# BB_AMP.net
KiCad netlist of a schematic drawn in Altium Designer
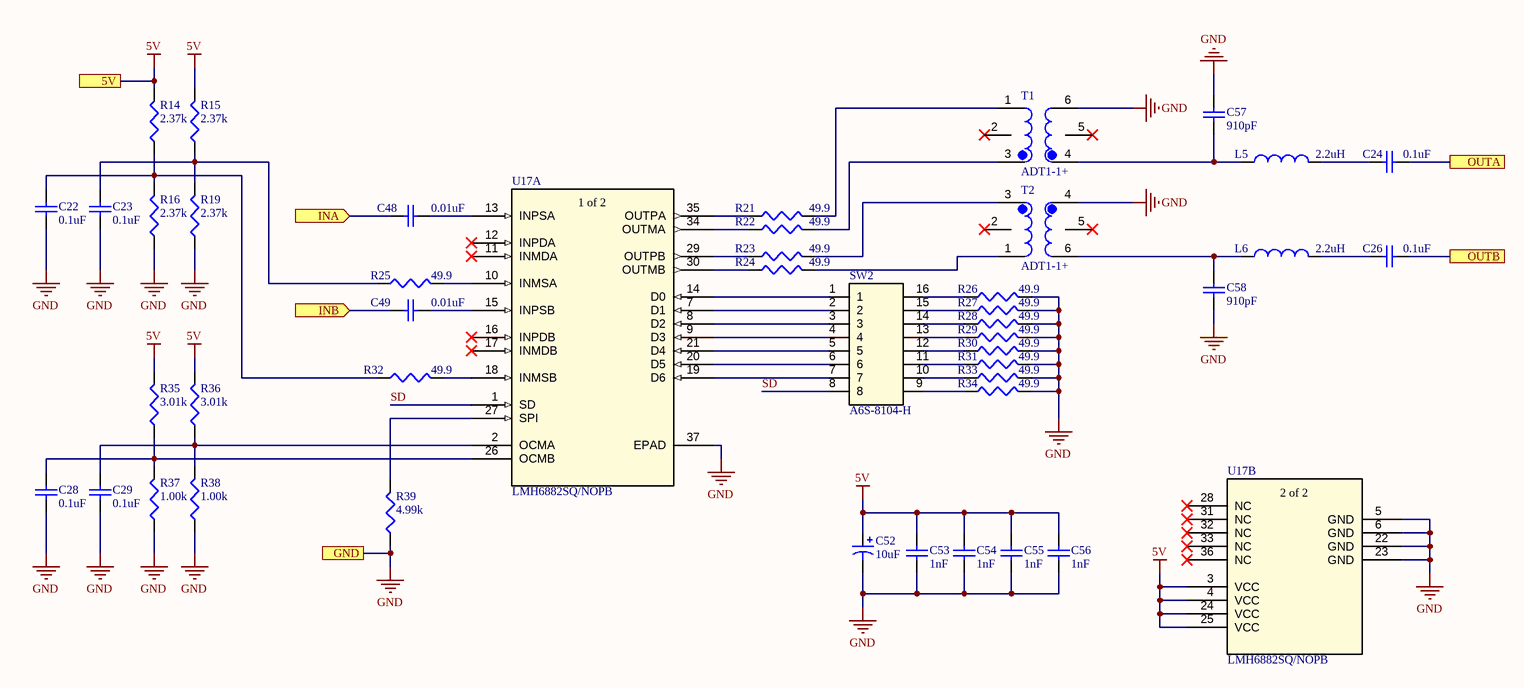
[diagram p0: BB_AMP.SchDoc]

(export (version "E")
  (design (tool "Eeschema 10.0.6"))
  (components
    (comp (ref "C22")
      (value "0.1uF")
      (footprint "SMD-0603")
      (description "Ceramic Capacitor 0603")
      (libsource (lib "LCR") (part "CAP0603"))
    )
    (comp (ref "C23")
      (value "0.1uF")
      (footprint "SMD-0603")
      (description "Ceramic Capacitor 0603")
      (libsource (lib "LCR") (part "CAP0603"))
    )
    (comp (ref "C24")
      (value "0.1uF")
      (footprint "SMD-0603")
      (description "Ceramic Capacitor 0603")
      (libsource (lib "LCR") (part "CAP0603"))
    )
    (comp (ref "C26")
      (value "0.1uF")
      (footprint "SMD-0603")
      (description "Ceramic Capacitor 0603")
      (libsource (lib "LCR") (part "CAP0603"))
    )
    (comp (ref "C28")
      (value "0.1uF")
      (footprint "SMD-0603")
      (description "Ceramic Capacitor 0603")
      (libsource (lib "LCR") (part "CAP0603"))
    )
    (comp (ref "C29")
      (value "0.1uF")
      (footprint "SMD-0603")
      (description "Ceramic Capacitor 0603")
      (libsource (lib "LCR") (part "CAP0603"))
    )
    (comp (ref "C48")
      (value "0.01uF")
      (footprint "SMD-0402")
      (description "Ceramic Capacitor 0402")
      (libsource (lib "LCR") (part "CAP0402"))
    )
    (comp (ref "C49")
      (value "0.01uF")
      (footprint "SMD-0402")
      (description "Ceramic Capacitor 0402")
      (libsource (lib "LCR") (part "CAP0402"))
    )
    (comp (ref "C52")
      (value "10uF")
      (footprint "CAP_TANT_1206_POL")
      (description "Polarized Cap, Size 1206 Imperial (3216 Metric), Tantalum")
      (libsource (lib "LCR") (part "CAP_TANT_1206"))
    )
    (comp (ref "C53")
      (value "1nF")
      (footprint "SMD-0402")
      (description "Ceramic Capacitor 0402")
      (libsource (lib "LCR") (part "CAP0402"))
    )
    (comp (ref "C54")
      (value "1nF")
      (footprint "SMD-0402")
      (description "Ceramic Capacitor 0402")
      (libsource (lib "LCR") (part "CAP0402"))
    )
    (comp (ref "C55")
      (value "1nF")
      (footprint "SMD-0402")
      (description "Ceramic Capacitor 0402")
      (libsource (lib "LCR") (part "CAP0402"))
    )
    (comp (ref "C56")
      (value "1nF")
      (footprint "SMD-0402")
      (description "Ceramic Capacitor 0402")
      (libsource (lib "LCR") (part "CAP0402"))
    )
    (comp (ref "C57")
      (value "910pF")
      (footprint "SMD-0603")
      (description "Ceramic Capacitor 0603")
      (libsource (lib "LCR") (part "CAP0603"))
    )
    (comp (ref "C58")
      (value "910pF")
      (footprint "SMD-0603")
      (description "Ceramic Capacitor 0603")
      (libsource (lib "LCR") (part "CAP0603"))
    )
    (comp (ref "L5")
      (value "2.2uH")
      (footprint "SMD-0603")
      (description "Inductor 0603")
      (libsource (lib "LCR") (part "L0603"))
    )
    (comp (ref "L6")
      (value "2.2uH")
      (footprint "SMD-0603")
      (description "Inductor 0603")
      (libsource (lib "LCR") (part "L0603"))
    )
    (comp (ref "R14")
      (value "2.37k")
      (footprint "SMD-0603")
      (description "Resistor-0603")
      (libsource (lib "LCR") (part "RES0603"))
    )
    (comp (ref "R15")
      (value "2.37k")
      (footprint "SMD-0603")
      (description "Resistor-0603")
      (libsource (lib "LCR") (part "RES0603"))
    )
    (comp (ref "R16")
      (value "2.37k")
      (footprint "SMD-0603")
      (description "Resistor-0603")
      (libsource (lib "LCR") (part "RES0603"))
    )
    (comp (ref "R19")
      (value "2.37k")
      (footprint "SMD-0603")
      (description "Resistor-0603")
      (libsource (lib "LCR") (part "RES0603"))
    )
    (comp (ref "R21")
      (value "49.9")
      (footprint "SMD-0402")
      (description "Resistor-0402")
      (libsource (lib "LCR") (part "RES0402"))
    )
    (comp (ref "R22")
      (value "49.9")
      (footprint "SMD-0402")
      (description "Resistor-0402")
      (libsource (lib "LCR") (part "RES0402"))
    )
    (comp (ref "R23")
      (value "49.9")
      (footprint "SMD-0402")
      (description "Resistor-0402")
      (libsource (lib "LCR") (part "RES0402"))
    )
    (comp (ref "R24")
      (value "49.9")
      (footprint "SMD-0402")
      (description "Resistor-0402")
      (libsource (lib "LCR") (part "RES0402"))
    )
    (comp (ref "R25")
      (value "49.9")
      (footprint "SMD-0402")
      (description "Resistor-0402")
      (libsource (lib "LCR") (part "RES0402"))
    )
    (comp (ref "R26")
      (value "49.9")
      (footprint "SMD-0603")
      (description "Resistor-0603")
      (libsource (lib "LCR") (part "RES0603"))
    )
    (comp (ref "R27")
      (value "49.9")
      (footprint "SMD-0603")
      (description "Resistor-0603")
      (libsource (lib "LCR") (part "RES0603"))
    )
    (comp (ref "R28")
      (value "49.9")
      (footprint "SMD-0603")
      (description "Resistor-0603")
      (libsource (lib "LCR") (part "RES0603"))
    )
    (comp (ref "R29")
      (value "49.9")
      (footprint "SMD-0603")
      (description "Resistor-0603")
      (libsource (lib "LCR") (part "RES0603"))
    )
    (comp (ref "R30")
      (value "49.9")
      (footprint "SMD-0603")
      (description "Resistor-0603")
      (libsource (lib "LCR") (part "RES0603"))
    )
    (comp (ref "R31")
      (value "49.9")
      (footprint "SMD-0603")
      (description "Resistor-0603")
      (libsource (lib "LCR") (part "RES0603"))
    )
    (comp (ref "R32")
      (value "49.9")
      (footprint "SMD-0402")
      (description "Resistor-0402")
      (libsource (lib "LCR") (part "RES0402"))
    )
    (comp (ref "R33")
      (value "49.9")
      (footprint "SMD-0603")
      (description "Resistor-0603")
      (libsource (lib "LCR") (part "RES0603"))
    )
    (comp (ref "R34")
      (value "49.9")
      (footprint "SMD-0603")
      (description "Resistor-0603")
      (libsource (lib "LCR") (part "RES0603"))
    )
    (comp (ref "R35")
      (value "3.01k")
      (footprint "SMD-0603")
      (description "Resistor-0603")
      (libsource (lib "LCR") (part "RES0603"))
    )
    (comp (ref "R36")
      (value "3.01k")
      (footprint "SMD-0603")
      (description "Resistor-0603")
      (libsource (lib "LCR") (part "RES0603"))
    )
    (comp (ref "R37")
      (value "1.00k")
      (footprint "SMD-0603")
      (description "Resistor-0603")
      (libsource (lib "LCR") (part "RES0603"))
    )
    (comp (ref "R38")
      (value "1.00k")
      (footprint "SMD-0603")
      (description "Resistor-0603")
      (libsource (lib "LCR") (part "RES0603"))
    )
    (comp (ref "R39")
      (value "4.99k")
      (footprint "SMD-0603")
      (description "Resistor-0603")
      (libsource (lib "LCR") (part "RES0603"))
    )
    (comp (ref "SW2")
      (value "A6S-8104-H")
      (footprint "A6S-8101-H")
      (description "Dip Switch SPST 8 Position Surface Mount Slide (Standard) Actuator 25mA 24VDC")
      (fields (field (name "COPYRIGHT") "Copyright (C) 2018 Accelerated Designs. All rights reserved"))
      (libsource (lib "Connectors") (part "A6S-8104-H"))
    )
    (comp (ref "T1")
      (value "ADT1-1+")
      (footprint "FullyDigital:XFMR_ADT1-1+")
      (description "RF Transformer, 50 ohm, 1:1, 0.15-400 MHz, SMT")
      (fields (field (name "MP") "ADT1-6T+") (field (name "MF") "Mini-Circuits"))
      (libsource (lib "") (part "ADT1-1+_1"))
    )
    (comp (ref "T2")
      (value "ADT1-1+")
      (footprint "FullyDigital:XFMR_ADT1-1+")
      (description "RF Transformer, 50 ohm, 1:1, 0.15-400 MHz, SMT")
      (fields (field (name "MP") "ADT1-6T+") (field (name "MF") "Mini-Circuits"))
      (libsource (lib "FullyDigital") (part "ADT1-1+"))
    )
    (comp (ref "U17")
      (value "LMH6882SQ/NOPB")
      (footprint "NJK36_TEX")
      (description "LMH6882 DC to 2.4-GHz, High-Linearity, Dual, Programmable Differential Amplifier")
      (fields (field (name "COPYRIGHT") "Copyright (C) 2018 Accelerated Designs. All rights reserved"))
      (libsource (lib "FullyDigital") (part "LMH6882"))
    )
  )
  (nets
    (net (code "1") (name "/INA") (class "Default")
      (node (ref "C48") (pin "1") (pinfunction "1_1") (pintype "passive"))
    )
    (net (code "2") (name "/INB") (class "Default")
      (node (ref "C49") (pin "1") (pinfunction "1_1") (pintype "passive"))
    )
    (net (code "3") (name "/OUTA") (class "Default")
      (node (ref "C24") (pin "2") (pinfunction "2_2") (pintype "passive"))
    )
    (net (code "4") (name "/OUTB") (class "Default")
      (node (ref "C26") (pin "2") (pinfunction "2_2") (pintype "passive"))
    )
    (net (code "5") (name "/SD") (class "Default")
      (node (ref "SW2") (pin "8") (pinfunction "8_8") (pintype "passive"))
      (node (ref "U17") (pin "1") (pinfunction "SD_1") (pintype "input"))
    )
    (net (code "6") (name "5V") (class "Default")
      (node (ref "C52") (pin "1") (pinfunction "1_1") (pintype "passive"))
      (node (ref "C53") (pin "2") (pinfunction "2_2") (pintype "passive"))
      (node (ref "C54") (pin "2") (pinfunction "2_2") (pintype "passive"))
      (node (ref "C55") (pin "2") (pinfunction "2_2") (pintype "passive"))
      (node (ref "C56") (pin "2") (pinfunction "2_2") (pintype "passive"))
      (node (ref "R14") (pin "2") (pinfunction "2_2") (pintype "passive"))
      (node (ref "R15") (pin "2") (pinfunction "2_2") (pintype "passive"))
      (node (ref "R35") (pin "2") (pinfunction "2_2") (pintype "passive"))
      (node (ref "R36") (pin "2") (pinfunction "2_2") (pintype "passive"))
      (node (ref "U17") (pin "24") (pinfunction "VCC_24") (pintype "power_in"))
      (node (ref "U17") (pin "25") (pinfunction "VCC_25") (pintype "power_in"))
      (node (ref "U17") (pin "3") (pinfunction "VCC_3") (pintype "power_in"))
      (node (ref "U17") (pin "4") (pinfunction "VCC_4") (pintype "power_in"))
    )
    (net (code "7") (name "GND") (class "Default")
      (node (ref "C22") (pin "1") (pinfunction "1_1") (pintype "passive"))
      (node (ref "C23") (pin "1") (pinfunction "1_1") (pintype "passive"))
      (node (ref "C28") (pin "1") (pinfunction "1_1") (pintype "passive"))
      (node (ref "C29") (pin "1") (pinfunction "1_1") (pintype "passive"))
      (node (ref "C52") (pin "2") (pinfunction "2_2") (pintype "passive"))
      (node (ref "C53") (pin "1") (pinfunction "1_1") (pintype "passive"))
      (node (ref "C54") (pin "1") (pinfunction "1_1") (pintype "passive"))
      (node (ref "C55") (pin "1") (pinfunction "1_1") (pintype "passive"))
      (node (ref "C56") (pin "1") (pinfunction "1_1") (pintype "passive"))
      (node (ref "C57") (pin "2") (pinfunction "2_2") (pintype "passive"))
      (node (ref "C58") (pin "1") (pinfunction "1_1") (pintype "passive"))
      (node (ref "R16") (pin "1") (pinfunction "1_1") (pintype "passive"))
      (node (ref "R19") (pin "1") (pinfunction "1_1") (pintype "passive"))
      (node (ref "R26") (pin "2") (pinfunction "2_2") (pintype "passive"))
      (node (ref "R27") (pin "2") (pinfunction "2_2") (pintype "passive"))
      (node (ref "R28") (pin "2") (pinfunction "2_2") (pintype "passive"))
      (node (ref "R29") (pin "2") (pinfunction "2_2") (pintype "passive"))
      (node (ref "R30") (pin "2") (pinfunction "2_2") (pintype "passive"))
      (node (ref "R31") (pin "2") (pinfunction "2_2") (pintype "passive"))
      (node (ref "R33") (pin "2") (pinfunction "2_2") (pintype "passive"))
      (node (ref "R34") (pin "2") (pinfunction "2_2") (pintype "passive"))
      (node (ref "R37") (pin "1") (pinfunction "1_1") (pintype "passive"))
      (node (ref "R38") (pin "1") (pinfunction "1_1") (pintype "passive"))
      (node (ref "R39") (pin "1") (pinfunction "1_1") (pintype "passive"))
      (node (ref "T1") (pin "6") (pinfunction "6_6") (pintype "passive"))
      (node (ref "T2") (pin "4") (pinfunction "4_4") (pintype "passive"))
      (node (ref "U17") (pin "22") (pinfunction "GND_22") (pintype "power_in"))
      (node (ref "U17") (pin "23") (pinfunction "GND_23") (pintype "power_in"))
      (node (ref "U17") (pin "37") (pinfunction "EPAD_37") (pintype "passive"))
      (node (ref "U17") (pin "5") (pinfunction "GND_5") (pintype "power_in"))
      (node (ref "U17") (pin "6") (pinfunction "GND_6") (pintype "power_in"))
    )
    (net (code "8") (name "Net-(C22-Pad2)") (class "Default")
      (node (ref "C22") (pin "2") (pinfunction "2_2") (pintype "passive"))
      (node (ref "R14") (pin "1") (pinfunction "1_1") (pintype "passive"))
      (node (ref "R16") (pin "2") (pinfunction "2_2") (pintype "passive"))
      (node (ref "R32") (pin "1") (pinfunction "1_1") (pintype "passive"))
    )
    (net (code "9") (name "Net-(C23-Pad2)") (class "Default")
      (node (ref "C23") (pin "2") (pinfunction "2_2") (pintype "passive"))
      (node (ref "R15") (pin "1") (pinfunction "1_1") (pintype "passive"))
      (node (ref "R19") (pin "2") (pinfunction "2_2") (pintype "passive"))
      (node (ref "R25") (pin "1") (pinfunction "1_1") (pintype "passive"))
    )
    (net (code "10") (name "Net-(C24-Pad1)") (class "Default")
      (node (ref "C24") (pin "1") (pinfunction "1_1") (pintype "passive"))
      (node (ref "L5") (pin "2") (pinfunction "2_2") (pintype "passive"))
    )
    (net (code "11") (name "Net-(C26-Pad1)") (class "Default")
      (node (ref "C26") (pin "1") (pinfunction "1_1") (pintype "passive"))
      (node (ref "L6") (pin "2") (pinfunction "2_2") (pintype "passive"))
    )
    (net (code "12") (name "Net-(C57-Pad1)") (class "Default")
      (node (ref "C57") (pin "1") (pinfunction "1_1") (pintype "passive"))
      (node (ref "L5") (pin "1") (pinfunction "1_1") (pintype "passive"))
      (node (ref "T1") (pin "4") (pinfunction "4_4") (pintype "passive"))
    )
    (net (code "13") (name "Net-(C58-Pad2)") (class "Default")
      (node (ref "C58") (pin "2") (pinfunction "2_2") (pintype "passive"))
      (node (ref "L6") (pin "1") (pinfunction "1_1") (pintype "passive"))
      (node (ref "T2") (pin "6") (pinfunction "6_6") (pintype "passive"))
    )
    (net (code "14") (name "Net-(R21-Pad2)") (class "Default")
      (node (ref "R21") (pin "2") (pinfunction "2_2") (pintype "passive"))
      (node (ref "T1") (pin "1") (pinfunction "1_1") (pintype "passive"))
    )
    (net (code "15") (name "Net-(R22-Pad2)") (class "Default")
      (node (ref "R22") (pin "2") (pinfunction "2_2") (pintype "passive"))
      (node (ref "T1") (pin "3") (pinfunction "3_3") (pintype "passive"))
    )
    (net (code "16") (name "Net-(R23-Pad2)") (class "Default")
      (node (ref "R23") (pin "2") (pinfunction "2_2") (pintype "passive"))
      (node (ref "T2") (pin "3") (pinfunction "3_3") (pintype "passive"))
    )
    (net (code "17") (name "Net-(R24-Pad2)") (class "Default")
      (node (ref "R24") (pin "2") (pinfunction "2_2") (pintype "passive"))
      (node (ref "T2") (pin "1") (pinfunction "1_1") (pintype "passive"))
    )
    (net (code "18") (name "Net-(R26-Pad1)") (class "Default")
      (node (ref "R26") (pin "1") (pinfunction "1_1") (pintype "passive"))
      (node (ref "SW2") (pin "16") (pinfunction "16_16") (pintype "passive"))
    )
    (net (code "19") (name "Net-(R27-Pad1)") (class "Default")
      (node (ref "R27") (pin "1") (pinfunction "1_1") (pintype "passive"))
      (node (ref "SW2") (pin "15") (pinfunction "15_15") (pintype "passive"))
    )
    (net (code "20") (name "Net-(R28-Pad1)") (class "Default")
      (node (ref "R28") (pin "1") (pinfunction "1_1") (pintype "passive"))
      (node (ref "SW2") (pin "14") (pinfunction "14_14") (pintype "passive"))
    )
    (net (code "21") (name "Net-(R29-Pad1)") (class "Default")
      (node (ref "R29") (pin "1") (pinfunction "1_1") (pintype "passive"))
      (node (ref "SW2") (pin "13") (pinfunction "13_13") (pintype "passive"))
    )
    (net (code "22") (name "Net-(R30-Pad1)") (class "Default")
      (node (ref "R30") (pin "1") (pinfunction "1_1") (pintype "passive"))
      (node (ref "SW2") (pin "12") (pinfunction "12_12") (pintype "passive"))
    )
    (net (code "23") (name "Net-(R31-Pad1)") (class "Default")
      (node (ref "R31") (pin "1") (pinfunction "1_1") (pintype "passive"))
      (node (ref "SW2") (pin "11") (pinfunction "11_11") (pintype "passive"))
    )
    (net (code "24") (name "Net-(R33-Pad1)") (class "Default")
      (node (ref "R33") (pin "1") (pinfunction "1_1") (pintype "passive"))
      (node (ref "SW2") (pin "10") (pinfunction "10_10") (pintype "passive"))
    )
    (net (code "25") (name "Net-(R34-Pad1)") (class "Default")
      (node (ref "R34") (pin "1") (pinfunction "1_1") (pintype "passive"))
      (node (ref "SW2") (pin "9") (pinfunction "9_9") (pintype "passive"))
    )
    (net (code "26") (name "Net-(U17A-D0)") (class "Default")
      (node (ref "SW2") (pin "1") (pinfunction "1_1") (pintype "passive"))
      (node (ref "U17") (pin "14") (pinfunction "D0_14") (pintype "input"))
    )
    (net (code "27") (name "Net-(U17A-D1)") (class "Default")
      (node (ref "SW2") (pin "2") (pinfunction "2_2") (pintype "passive"))
      (node (ref "U17") (pin "7") (pinfunction "D1_7") (pintype "input"))
    )
    (net (code "28") (name "Net-(U17A-D2)") (class "Default")
      (node (ref "SW2") (pin "3") (pinfunction "3_3") (pintype "passive"))
      (node (ref "U17") (pin "8") (pinfunction "D2_8") (pintype "input"))
    )
    (net (code "29") (name "Net-(U17A-D3)") (class "Default")
      (node (ref "SW2") (pin "4") (pinfunction "4_4") (pintype "passive"))
      (node (ref "U17") (pin "9") (pinfunction "D3_9") (pintype "input"))
    )
    (net (code "30") (name "Net-(U17A-D4)") (class "Default")
      (node (ref "SW2") (pin "5") (pinfunction "5_5") (pintype "passive"))
      (node (ref "U17") (pin "21") (pinfunction "D4_21") (pintype "input"))
    )
    (net (code "31") (name "Net-(U17A-D5)") (class "Default")
      (node (ref "SW2") (pin "6") (pinfunction "6_6") (pintype "passive"))
      (node (ref "U17") (pin "20") (pinfunction "D5_20") (pintype "input"))
    )
    (net (code "32") (name "Net-(U17A-D6)") (class "Default")
      (node (ref "SW2") (pin "7") (pinfunction "7_7") (pintype "passive"))
      (node (ref "U17") (pin "19") (pinfunction "D6_19") (pintype "input"))
    )
    (net (code "33") (name "Net-(U17A-INMSA)") (class "Default")
      (node (ref "R25") (pin "2") (pinfunction "2_2") (pintype "passive"))
      (node (ref "U17") (pin "10") (pinfunction "INMSA_10") (pintype "input"))
    )
    (net (code "34") (name "Net-(U17A-INMSB)") (class "Default")
      (node (ref "R32") (pin "2") (pinfunction "2_2") (pintype "passive"))
      (node (ref "U17") (pin "18") (pinfunction "INMSB_18") (pintype "input"))
    )
    (net (code "35") (name "Net-(U17A-INPSA)") (class "Default")
      (node (ref "C48") (pin "2") (pinfunction "2_2") (pintype "passive"))
      (node (ref "U17") (pin "13") (pinfunction "INPSA_13") (pintype "input"))
    )
    (net (code "36") (name "Net-(U17A-INPSB)") (class "Default")
      (node (ref "C49") (pin "2") (pinfunction "2_2") (pintype "passive"))
      (node (ref "U17") (pin "15") (pinfunction "INPSB_15") (pintype "input"))
    )
    (net (code "37") (name "Net-(U17A-OCMA)") (class "Default")
      (node (ref "C29") (pin "2") (pinfunction "2_2") (pintype "passive"))
      (node (ref "R36") (pin "1") (pinfunction "1_1") (pintype "passive"))
      (node (ref "R38") (pin "2") (pinfunction "2_2") (pintype "passive"))
      (node (ref "U17") (pin "2") (pinfunction "OCMA_2") (pintype "passive"))
    )
    (net (code "38") (name "Net-(U17A-OCMB)") (class "Default")
      (node (ref "C28") (pin "2") (pinfunction "2_2") (pintype "passive"))
      (node (ref "R35") (pin "1") (pinfunction "1_1") (pintype "passive"))
      (node (ref "R37") (pin "2") (pinfunction "2_2") (pintype "passive"))
      (node (ref "U17") (pin "26") (pinfunction "OCMB_26") (pintype "passive"))
    )
    (net (code "39") (name "Net-(U17A-OUTMA)") (class "Default")
      (node (ref "R22") (pin "1") (pinfunction "1_1") (pintype "passive"))
      (node (ref "U17") (pin "34") (pinfunction "OUTMA_34") (pintype "output"))
    )
    (net (code "40") (name "Net-(U17A-OUTMB)") (class "Default")
      (node (ref "R24") (pin "1") (pinfunction "1_1") (pintype "passive"))
      (node (ref "U17") (pin "30") (pinfunction "OUTMB_30") (pintype "output"))
    )
    (net (code "41") (name "Net-(U17A-OUTPA)") (class "Default")
      (node (ref "R21") (pin "1") (pinfunction "1_1") (pintype "passive"))
      (node (ref "U17") (pin "35") (pinfunction "OUTPA_35") (pintype "output"))
    )
    (net (code "42") (name "Net-(U17A-OUTPB)") (class "Default")
      (node (ref "R23") (pin "1") (pinfunction "1_1") (pintype "passive"))
      (node (ref "U17") (pin "29") (pinfunction "OUTPB_29") (pintype "output"))
    )
    (net (code "43") (name "Net-(U17A-SPI)") (class "Default")
      (node (ref "R39") (pin "2") (pinfunction "2_2") (pintype "passive"))
      (node (ref "U17") (pin "27") (pinfunction "SPI_27") (pintype "input"))
    )
    (net (code "44") (name "unconnected-(T1-NC-Pad2)") (class "Default")
      (node (ref "T1") (pin "2") (pinfunction "NC_2") (pintype "passive+no_connect"))
    )
    (net (code "45") (name "unconnected-(T1-Pad5)") (class "Default")
      (node (ref "T1") (pin "5") (pinfunction "5_5") (pintype "passive+no_connect"))
    )
    (net (code "46") (name "unconnected-(T2-NC-Pad2)") (class "Default")
      (node (ref "T2") (pin "2") (pinfunction "NC_2") (pintype "passive+no_connect"))
    )
    (net (code "47") (name "unconnected-(T2-Pad5)") (class "Default")
      (node (ref "T2") (pin "5") (pinfunction "5_5") (pintype "passive+no_connect"))
    )
    (net (code "48") (name "unconnected-(U17A-INMDA-Pad11)") (class "Default")
      (node (ref "U17") (pin "11") (pinfunction "INMDA_11") (pintype "input+no_connect"))
    )
    (net (code "49") (name "unconnected-(U17A-INMDB-Pad17)") (class "Default")
      (node (ref "U17") (pin "17") (pinfunction "INMDB_17") (pintype "input+no_connect"))
    )
    (net (code "50") (name "unconnected-(U17A-INPDA-Pad12)") (class "Default")
      (node (ref "U17") (pin "12") (pinfunction "INPDA_12") (pintype "input+no_connect"))
    )
    (net (code "51") (name "unconnected-(U17A-INPDB-Pad16)") (class "Default")
      (node (ref "U17") (pin "16") (pinfunction "INPDB_16") (pintype "input+no_connect"))
    )
    (net (code "52") (name "unconnected-(U17B-NC-Pad28)") (class "Default")
      (node (ref "U17") (pin "28") (pinfunction "NC_28") (pintype "passive+no_connect"))
    )
    (net (code "53") (name "unconnected-(U17B-NC-Pad31)") (class "Default")
      (node (ref "U17") (pin "31") (pinfunction "NC_31") (pintype "passive+no_connect"))
    )
    (net (code "54") (name "unconnected-(U17B-NC-Pad32)") (class "Default")
      (node (ref "U17") (pin "32") (pinfunction "NC_32") (pintype "passive+no_connect"))
    )
    (net (code "55") (name "unconnected-(U17B-NC-Pad33)") (class "Default")
      (node (ref "U17") (pin "33") (pinfunction "NC_33") (pintype "passive+no_connect"))
    )
    (net (code "56") (name "unconnected-(U17B-NC-Pad36)") (class "Default")
      (node (ref "U17") (pin "36") (pinfunction "NC_36") (pintype "passive+no_connect"))
    )
  )
)
